# proximity_switch_connector.net
KiCad netlist of a schematic drawn in EAGLE
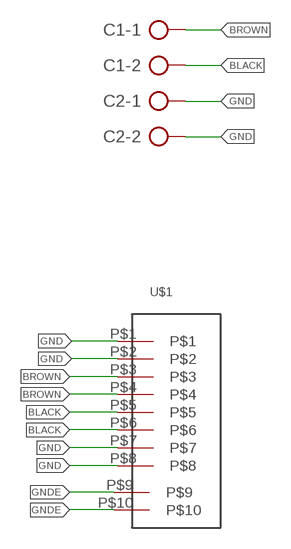
[diagram p0: schematic, sheet 1]

(export (version "E")
  (design (tool "Eeschema 10.0.6"))
  (components
    (comp (ref "C1")
      (value "AK300/2")
      (footprint "eagle-import:AK300_2")
      (libsource (lib "eagle-import") (part "AK300/2"))
    )
    (comp (ref "C2")
      (value "AK300/2")
      (footprint "eagle-import:AK300_2")
      (libsource (lib "eagle-import") (part "AK300/2"))
    )
    (comp (ref "U$1")
      (value "RJ45_SMTRJ")
      (footprint "eagle-import:RJ45_SMT")
      (libsource (lib "eagle-import") (part "RJ45_SMTRJ"))
    )
  )
  (nets
    (net (code "1") (name "BLACK") (class "Default")
      (node (ref "C1") (pin "2") (pinfunction "KL_2") (pintype "passive"))
      (node (ref "U$1") (pin "P$5") (pinfunction "P$5_P$5") (pintype "bidirectional"))
      (node (ref "U$1") (pin "P$6") (pinfunction "P$6_P$6") (pintype "bidirectional"))
    )
    (net (code "2") (name "BROWN") (class "Default")
      (node (ref "C1") (pin "1") (pinfunction "KL_1") (pintype "passive"))
      (node (ref "U$1") (pin "P$3") (pinfunction "P$3_P$3") (pintype "bidirectional"))
      (node (ref "U$1") (pin "P$4") (pinfunction "P$4_P$4") (pintype "bidirectional"))
    )
    (net (code "3") (name "GND") (class "Default")
      (node (ref "C2") (pin "1") (pinfunction "KL_1") (pintype "passive"))
      (node (ref "C2") (pin "2") (pinfunction "KL_2") (pintype "passive"))
      (node (ref "U$1") (pin "P$1") (pinfunction "P$1_P$1") (pintype "bidirectional"))
      (node (ref "U$1") (pin "P$2") (pinfunction "P$2_P$2") (pintype "bidirectional"))
      (node (ref "U$1") (pin "P$7") (pinfunction "P$7_P$7") (pintype "bidirectional"))
      (node (ref "U$1") (pin "P$8") (pinfunction "P$8_P$8") (pintype "bidirectional"))
    )
    (net (code "4") (name "GNDE") (class "Default")
      (node (ref "U$1") (pin "P$10") (pinfunction "P$10_P$10") (pintype "bidirectional"))
      (node (ref "U$1") (pin "P$9") (pinfunction "P$9_P$9") (pintype "bidirectional"))
    )
  )
)
